# PowerBoard.net
KiCad netlist of a schematic drawn in Altium Designer
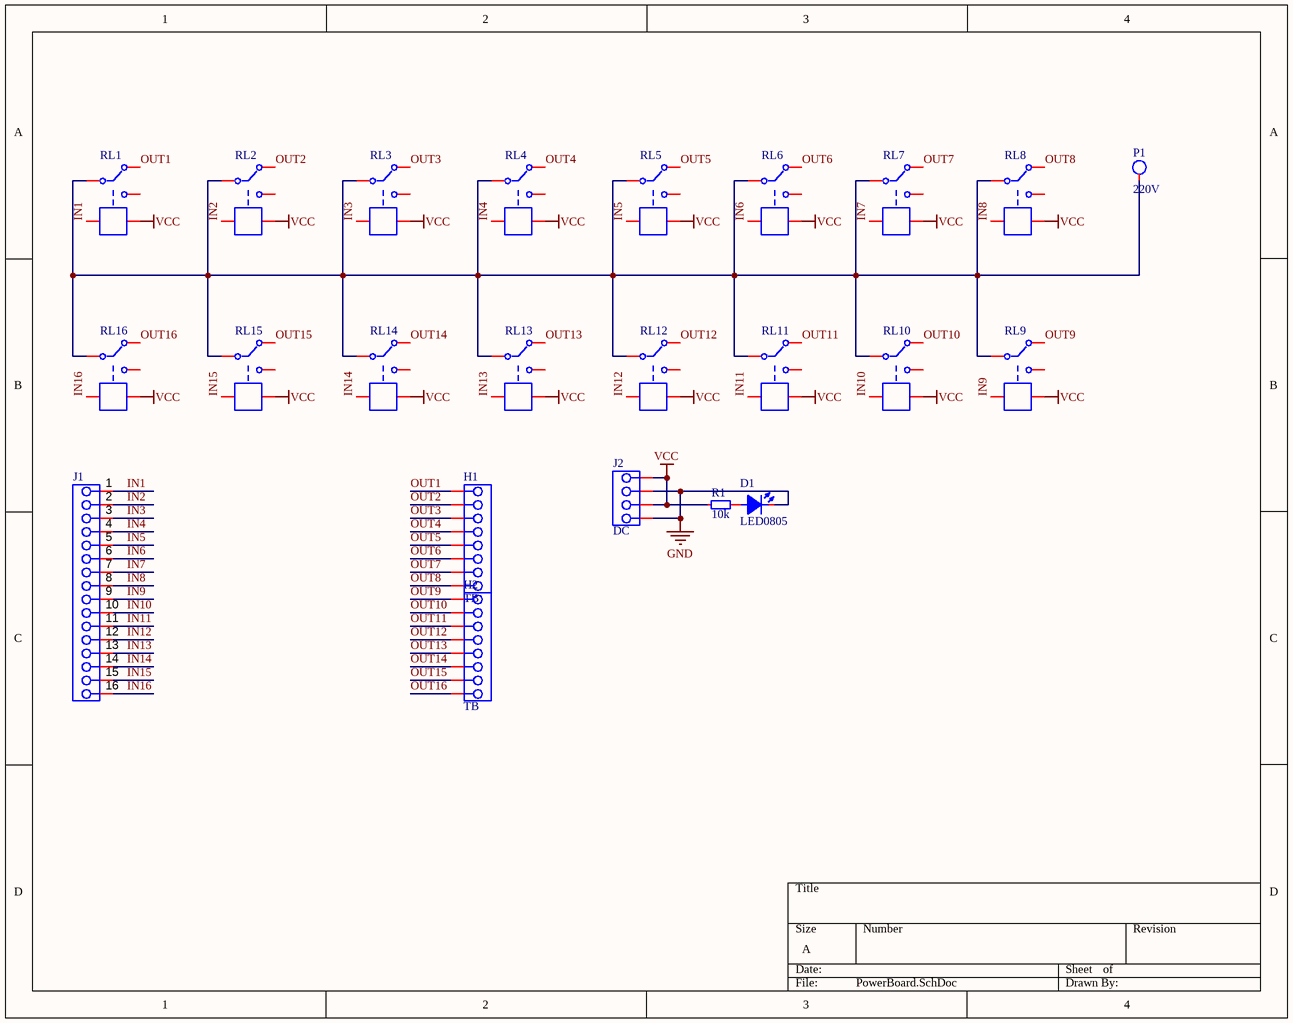
[diagram p0: PowerBoard.SchDoc]

(export (version "E")
  (design (tool "Eeschema 10.0.6"))
  (components
    (comp (ref "D1")
      (value "LED0805")
      (footprint "L0805RED")
      (libsource (lib "MyAltiumLibrary") (part "LED0805"))
    )
    (comp (ref "H1")
      (value "TB")
      (footprint "TERMINAL-BLOCK-7.62MM -08PIN")
      (libsource (lib "MyAltiumLibrary") (part "TERMINAL-BLOCK-7.62MM-08PIN"))
    )
    (comp (ref "H2")
      (value "TB")
      (footprint "TERMINAL-BLOCK-7.62MM -08PIN")
      (libsource (lib "MyAltiumLibrary") (part "TERMINAL-BLOCK-7.62MM-08PIN"))
    )
    (comp (ref "J1")
      (value "HEADER-FEMALE-2.54MM")
      (footprint "HEADER-FEMALE-16PINS-2.54MM")
      (libsource (lib "MyAltiumLibrary") (part "HEADER-FEMALE-16PINS-2.54MM"))
    )
    (comp (ref "J2")
      (value "DC")
      (footprint "DG350-3.5-04P-12-00AH")
      (libsource (lib "MyAltiumLibrary") (part "DGxxx_04P"))
    )
    (comp (ref "P1")
      (value "220V")
      (footprint "SolderPoint")
      (libsource (lib "MyAltiumLibrary") (part "SolderPoint"))
    )
    (comp (ref "R1")
      (value "10k")
      (footprint "R0805")
      (libsource (lib "MyAltiumLibrary") (part "Resistors-SMD"))
    )
    (comp (ref "RL1")
      (value "Relay-SONGLE-SRD-05VDC")
      (footprint "RELAY-SONGLE-SRD-05VDC_BLUE")
      (libsource (lib "MyAltiumLibrary") (part "Relay-SONGLE-SRD-05VDC"))
    )
    (comp (ref "RL2")
      (value "Relay-SONGLE-SRD-05VDC")
      (footprint "RELAY-SONGLE-SRD-05VDC_BLUE")
      (libsource (lib "MyAltiumLibrary") (part "Relay-SONGLE-SRD-05VDC"))
    )
    (comp (ref "RL3")
      (value "Relay-SONGLE-SRD-05VDC")
      (footprint "RELAY-SONGLE-SRD-05VDC_BLUE")
      (libsource (lib "MyAltiumLibrary") (part "Relay-SONGLE-SRD-05VDC"))
    )
    (comp (ref "RL4")
      (value "Relay-SONGLE-SRD-05VDC")
      (footprint "RELAY-SONGLE-SRD-05VDC_BLUE")
      (libsource (lib "MyAltiumLibrary") (part "Relay-SONGLE-SRD-05VDC"))
    )
    (comp (ref "RL5")
      (value "Relay-SONGLE-SRD-05VDC")
      (footprint "RELAY-SONGLE-SRD-05VDC_BLUE")
      (libsource (lib "MyAltiumLibrary") (part "Relay-SONGLE-SRD-05VDC"))
    )
    (comp (ref "RL6")
      (value "Relay-SONGLE-SRD-05VDC")
      (footprint "RELAY-SONGLE-SRD-05VDC_BLUE")
      (libsource (lib "MyAltiumLibrary") (part "Relay-SONGLE-SRD-05VDC"))
    )
    (comp (ref "RL7")
      (value "Relay-SONGLE-SRD-05VDC")
      (footprint "RELAY-SONGLE-SRD-05VDC_BLUE")
      (libsource (lib "MyAltiumLibrary") (part "Relay-SONGLE-SRD-05VDC"))
    )
    (comp (ref "RL8")
      (value "Relay-SONGLE-SRD-05VDC")
      (footprint "RELAY-SONGLE-SRD-05VDC_BLUE")
      (libsource (lib "MyAltiumLibrary") (part "Relay-SONGLE-SRD-05VDC"))
    )
    (comp (ref "RL9")
      (value "Relay-SONGLE-SRD-05VDC")
      (footprint "RELAY-SONGLE-SRD-05VDC_BLUE")
      (libsource (lib "MyAltiumLibrary") (part "Relay-SONGLE-SRD-05VDC"))
    )
    (comp (ref "RL10")
      (value "Relay-SONGLE-SRD-05VDC")
      (footprint "RELAY-SONGLE-SRD-05VDC_BLUE")
      (libsource (lib "MyAltiumLibrary") (part "Relay-SONGLE-SRD-05VDC"))
    )
    (comp (ref "RL11")
      (value "Relay-SONGLE-SRD-05VDC")
      (footprint "RELAY-SONGLE-SRD-05VDC_BLUE")
      (libsource (lib "MyAltiumLibrary") (part "Relay-SONGLE-SRD-05VDC"))
    )
    (comp (ref "RL12")
      (value "Relay-SONGLE-SRD-05VDC")
      (footprint "RELAY-SONGLE-SRD-05VDC_BLUE")
      (libsource (lib "MyAltiumLibrary") (part "Relay-SONGLE-SRD-05VDC"))
    )
    (comp (ref "RL13")
      (value "Relay-SONGLE-SRD-05VDC")
      (footprint "RELAY-SONGLE-SRD-05VDC_BLUE")
      (libsource (lib "MyAltiumLibrary") (part "Relay-SONGLE-SRD-05VDC"))
    )
    (comp (ref "RL14")
      (value "Relay-SONGLE-SRD-05VDC")
      (footprint "RELAY-SONGLE-SRD-05VDC_BLUE")
      (libsource (lib "MyAltiumLibrary") (part "Relay-SONGLE-SRD-05VDC"))
    )
    (comp (ref "RL15")
      (value "Relay-SONGLE-SRD-05VDC")
      (footprint "RELAY-SONGLE-SRD-05VDC_BLUE")
      (libsource (lib "MyAltiumLibrary") (part "Relay-SONGLE-SRD-05VDC"))
    )
    (comp (ref "RL16")
      (value "Relay-SONGLE-SRD-05VDC")
      (footprint "RELAY-SONGLE-SRD-05VDC_BLUE")
      (libsource (lib "MyAltiumLibrary") (part "Relay-SONGLE-SRD-05VDC"))
    )
  )
  (nets
    (net (code "1") (name "/IN1") (class "Default")
      (node (ref "J1") (pin "1") (pinfunction "1_1") (pintype "passive"))
      (node (ref "RL1") (pin "1") (pinfunction "1_1") (pintype "passive"))
    )
    (net (code "2") (name "/IN2") (class "Default")
      (node (ref "J1") (pin "2") (pinfunction "2_2") (pintype "passive"))
      (node (ref "RL2") (pin "1") (pinfunction "1_1") (pintype "passive"))
    )
    (net (code "3") (name "/IN3") (class "Default")
      (node (ref "J1") (pin "3") (pinfunction "3_3") (pintype "passive"))
      (node (ref "RL3") (pin "1") (pinfunction "1_1") (pintype "passive"))
    )
    (net (code "4") (name "/IN4") (class "Default")
      (node (ref "J1") (pin "4") (pinfunction "4_4") (pintype "passive"))
      (node (ref "RL4") (pin "1") (pinfunction "1_1") (pintype "passive"))
    )
    (net (code "5") (name "/IN5") (class "Default")
      (node (ref "J1") (pin "5") (pinfunction "5_5") (pintype "passive"))
      (node (ref "RL5") (pin "1") (pinfunction "1_1") (pintype "passive"))
    )
    (net (code "6") (name "/IN6") (class "Default")
      (node (ref "J1") (pin "6") (pinfunction "6_6") (pintype "passive"))
      (node (ref "RL6") (pin "1") (pinfunction "1_1") (pintype "passive"))
    )
    (net (code "7") (name "/IN7") (class "Default")
      (node (ref "J1") (pin "7") (pinfunction "7_7") (pintype "passive"))
      (node (ref "RL7") (pin "1") (pinfunction "1_1") (pintype "passive"))
    )
    (net (code "8") (name "/IN8") (class "Default")
      (node (ref "J1") (pin "8") (pinfunction "8_8") (pintype "passive"))
      (node (ref "RL8") (pin "1") (pinfunction "1_1") (pintype "passive"))
    )
    (net (code "9") (name "/IN9") (class "Default")
      (node (ref "J1") (pin "9") (pinfunction "9_9") (pintype "passive"))
      (node (ref "RL9") (pin "1") (pinfunction "1_1") (pintype "passive"))
    )
    (net (code "10") (name "/IN10") (class "Default")
      (node (ref "J1") (pin "10") (pinfunction "10_10") (pintype "passive"))
      (node (ref "RL10") (pin "1") (pinfunction "1_1") (pintype "passive"))
    )
    (net (code "11") (name "/IN11") (class "Default")
      (node (ref "J1") (pin "11") (pinfunction "11_11") (pintype "passive"))
      (node (ref "RL11") (pin "1") (pinfunction "1_1") (pintype "passive"))
    )
    (net (code "12") (name "/IN12") (class "Default")
      (node (ref "J1") (pin "12") (pinfunction "12_12") (pintype "passive"))
      (node (ref "RL12") (pin "1") (pinfunction "1_1") (pintype "passive"))
    )
    (net (code "13") (name "/IN13") (class "Default")
      (node (ref "J1") (pin "13") (pinfunction "13_13") (pintype "passive"))
      (node (ref "RL13") (pin "1") (pinfunction "1_1") (pintype "passive"))
    )
    (net (code "14") (name "/IN14") (class "Default")
      (node (ref "J1") (pin "14") (pinfunction "14_14") (pintype "passive"))
      (node (ref "RL14") (pin "1") (pinfunction "1_1") (pintype "passive"))
    )
    (net (code "15") (name "/IN15") (class "Default")
      (node (ref "J1") (pin "15") (pinfunction "15_15") (pintype "passive"))
      (node (ref "RL15") (pin "1") (pinfunction "1_1") (pintype "passive"))
    )
    (net (code "16") (name "/IN16") (class "Default")
      (node (ref "J1") (pin "16") (pinfunction "16_16") (pintype "passive"))
      (node (ref "RL16") (pin "1") (pinfunction "1_1") (pintype "passive"))
    )
    (net (code "17") (name "/OUT1") (class "Default")
      (node (ref "H1") (pin "8") (pinfunction "8_8") (pintype "passive"))
      (node (ref "RL1") (pin "5") (pinfunction "5_5") (pintype "passive"))
    )
    (net (code "18") (name "/OUT2") (class "Default")
      (node (ref "H1") (pin "7") (pinfunction "7_7") (pintype "passive"))
      (node (ref "RL2") (pin "5") (pinfunction "5_5") (pintype "passive"))
    )
    (net (code "19") (name "/OUT3") (class "Default")
      (node (ref "H1") (pin "6") (pinfunction "6_6") (pintype "passive"))
      (node (ref "RL3") (pin "5") (pinfunction "5_5") (pintype "passive"))
    )
    (net (code "20") (name "/OUT4") (class "Default")
      (node (ref "H1") (pin "5") (pinfunction "5_5") (pintype "passive"))
      (node (ref "RL4") (pin "5") (pinfunction "5_5") (pintype "passive"))
    )
    (net (code "21") (name "/OUT5") (class "Default")
      (node (ref "H1") (pin "4") (pinfunction "4_4") (pintype "passive"))
      (node (ref "RL5") (pin "5") (pinfunction "5_5") (pintype "passive"))
    )
    (net (code "22") (name "/OUT6") (class "Default")
      (node (ref "H1") (pin "3") (pinfunction "3_3") (pintype "passive"))
      (node (ref "RL6") (pin "5") (pinfunction "5_5") (pintype "passive"))
    )
    (net (code "23") (name "/OUT7") (class "Default")
      (node (ref "H1") (pin "2") (pinfunction "2_2") (pintype "passive"))
      (node (ref "RL7") (pin "5") (pinfunction "5_5") (pintype "passive"))
    )
    (net (code "24") (name "/OUT8") (class "Default")
      (node (ref "H1") (pin "1") (pinfunction "1_1") (pintype "passive"))
      (node (ref "RL8") (pin "5") (pinfunction "5_5") (pintype "passive"))
    )
    (net (code "25") (name "/OUT9") (class "Default")
      (node (ref "H2") (pin "8") (pinfunction "8_8") (pintype "passive"))
      (node (ref "RL9") (pin "5") (pinfunction "5_5") (pintype "passive"))
    )
    (net (code "26") (name "/OUT10") (class "Default")
      (node (ref "H2") (pin "7") (pinfunction "7_7") (pintype "passive"))
      (node (ref "RL10") (pin "5") (pinfunction "5_5") (pintype "passive"))
    )
    (net (code "27") (name "/OUT11") (class "Default")
      (node (ref "H2") (pin "6") (pinfunction "6_6") (pintype "passive"))
      (node (ref "RL11") (pin "5") (pinfunction "5_5") (pintype "passive"))
    )
    (net (code "28") (name "/OUT12") (class "Default")
      (node (ref "H2") (pin "5") (pinfunction "5_5") (pintype "passive"))
      (node (ref "RL12") (pin "5") (pinfunction "5_5") (pintype "passive"))
    )
    (net (code "29") (name "/OUT13") (class "Default")
      (node (ref "H2") (pin "4") (pinfunction "4_4") (pintype "passive"))
      (node (ref "RL13") (pin "5") (pinfunction "5_5") (pintype "passive"))
    )
    (net (code "30") (name "/OUT14") (class "Default")
      (node (ref "H2") (pin "3") (pinfunction "3_3") (pintype "passive"))
      (node (ref "RL14") (pin "5") (pinfunction "5_5") (pintype "passive"))
    )
    (net (code "31") (name "/OUT15") (class "Default")
      (node (ref "H2") (pin "2") (pinfunction "2_2") (pintype "passive"))
      (node (ref "RL15") (pin "5") (pinfunction "5_5") (pintype "passive"))
    )
    (net (code "32") (name "/OUT16") (class "Default")
      (node (ref "H2") (pin "1") (pinfunction "1_1") (pintype "passive"))
      (node (ref "RL16") (pin "5") (pinfunction "5_5") (pintype "passive"))
    )
    (net (code "33") (name "GND") (class "Default")
      (node (ref "D1") (pin "2") (pinfunction "K_2") (pintype "passive"))
      (node (ref "J2") (pin "2") (pinfunction "2_2") (pintype "passive"))
      (node (ref "J2") (pin "4") (pinfunction "4_4") (pintype "passive"))
    )
    (net (code "34") (name "Net-(D1-A)") (class "Default")
      (node (ref "D1") (pin "1") (pinfunction "A_1") (pintype "passive"))
      (node (ref "R1") (pin "2") (pinfunction "2_2") (pintype "passive"))
    )
    (net (code "35") (name "Net-(P1-Pad1)") (class "Default")
      (node (ref "P1") (pin "1") (pinfunction "1_1") (pintype "passive"))
      (node (ref "RL1") (pin "2") (pinfunction "2_2") (pintype "passive"))
      (node (ref "RL10") (pin "2") (pinfunction "2_2") (pintype "passive"))
      (node (ref "RL11") (pin "2") (pinfunction "2_2") (pintype "passive"))
      (node (ref "RL12") (pin "2") (pinfunction "2_2") (pintype "passive"))
      (node (ref "RL13") (pin "2") (pinfunction "2_2") (pintype "passive"))
      (node (ref "RL14") (pin "2") (pinfunction "2_2") (pintype "passive"))
      (node (ref "RL15") (pin "2") (pinfunction "2_2") (pintype "passive"))
      (node (ref "RL16") (pin "2") (pinfunction "2_2") (pintype "passive"))
      (node (ref "RL2") (pin "2") (pinfunction "2_2") (pintype "passive"))
      (node (ref "RL3") (pin "2") (pinfunction "2_2") (pintype "passive"))
      (node (ref "RL4") (pin "2") (pinfunction "2_2") (pintype "passive"))
      (node (ref "RL5") (pin "2") (pinfunction "2_2") (pintype "passive"))
      (node (ref "RL6") (pin "2") (pinfunction "2_2") (pintype "passive"))
      (node (ref "RL7") (pin "2") (pinfunction "2_2") (pintype "passive"))
      (node (ref "RL8") (pin "2") (pinfunction "2_2") (pintype "passive"))
      (node (ref "RL9") (pin "2") (pinfunction "2_2") (pintype "passive"))
    )
    (net (code "36") (name "VCC") (class "Default")
      (node (ref "J2") (pin "1") (pinfunction "1_1") (pintype "passive"))
      (node (ref "J2") (pin "3") (pinfunction "3_3") (pintype "passive"))
      (node (ref "R1") (pin "1") (pinfunction "1_1") (pintype "passive"))
      (node (ref "RL1") (pin "3") (pinfunction "3_3") (pintype "passive"))
      (node (ref "RL10") (pin "3") (pinfunction "3_3") (pintype "passive"))
      (node (ref "RL11") (pin "3") (pinfunction "3_3") (pintype "passive"))
      (node (ref "RL12") (pin "3") (pinfunction "3_3") (pintype "passive"))
      (node (ref "RL13") (pin "3") (pinfunction "3_3") (pintype "passive"))
      (node (ref "RL14") (pin "3") (pinfunction "3_3") (pintype "passive"))
      (node (ref "RL15") (pin "3") (pinfunction "3_3") (pintype "passive"))
      (node (ref "RL16") (pin "3") (pinfunction "3_3") (pintype "passive"))
      (node (ref "RL2") (pin "3") (pinfunction "3_3") (pintype "passive"))
      (node (ref "RL3") (pin "3") (pinfunction "3_3") (pintype "passive"))
      (node (ref "RL4") (pin "3") (pinfunction "3_3") (pintype "passive"))
      (node (ref "RL5") (pin "3") (pinfunction "3_3") (pintype "passive"))
      (node (ref "RL6") (pin "3") (pinfunction "3_3") (pintype "passive"))
      (node (ref "RL7") (pin "3") (pinfunction "3_3") (pintype "passive"))
      (node (ref "RL8") (pin "3") (pinfunction "3_3") (pintype "passive"))
      (node (ref "RL9") (pin "3") (pinfunction "3_3") (pintype "passive"))
    )
    (net (code "37") (name "unconnected-(RL1-Pad4)") (class "Default")
      (node (ref "RL1") (pin "4") (pinfunction "4_4") (pintype "passive"))
    )
    (net (code "38") (name "unconnected-(RL2-Pad4)") (class "Default")
      (node (ref "RL2") (pin "4") (pinfunction "4_4") (pintype "passive"))
    )
    (net (code "39") (name "unconnected-(RL3-Pad4)") (class "Default")
      (node (ref "RL3") (pin "4") (pinfunction "4_4") (pintype "passive"))
    )
    (net (code "40") (name "unconnected-(RL4-Pad4)") (class "Default")
      (node (ref "RL4") (pin "4") (pinfunction "4_4") (pintype "passive"))
    )
    (net (code "41") (name "unconnected-(RL5-Pad4)") (class "Default")
      (node (ref "RL5") (pin "4") (pinfunction "4_4") (pintype "passive"))
    )
    (net (code "42") (name "unconnected-(RL6-Pad4)") (class "Default")
      (node (ref "RL6") (pin "4") (pinfunction "4_4") (pintype "passive"))
    )
    (net (code "43") (name "unconnected-(RL7-Pad4)") (class "Default")
      (node (ref "RL7") (pin "4") (pinfunction "4_4") (pintype "passive"))
    )
    (net (code "44") (name "unconnected-(RL8-Pad4)") (class "Default")
      (node (ref "RL8") (pin "4") (pinfunction "4_4") (pintype "passive"))
    )
    (net (code "45") (name "unconnected-(RL9-Pad4)") (class "Default")
      (node (ref "RL9") (pin "4") (pinfunction "4_4") (pintype "passive"))
    )
    (net (code "46") (name "unconnected-(RL10-Pad4)") (class "Default")
      (node (ref "RL10") (pin "4") (pinfunction "4_4") (pintype "passive"))
    )
    (net (code "47") (name "unconnected-(RL11-Pad4)") (class "Default")
      (node (ref "RL11") (pin "4") (pinfunction "4_4") (pintype "passive"))
    )
    (net (code "48") (name "unconnected-(RL12-Pad4)") (class "Default")
      (node (ref "RL12") (pin "4") (pinfunction "4_4") (pintype "passive"))
    )
    (net (code "49") (name "unconnected-(RL13-Pad4)") (class "Default")
      (node (ref "RL13") (pin "4") (pinfunction "4_4") (pintype "passive"))
    )
    (net (code "50") (name "unconnected-(RL14-Pad4)") (class "Default")
      (node (ref "RL14") (pin "4") (pinfunction "4_4") (pintype "passive"))
    )
    (net (code "51") (name "unconnected-(RL15-Pad4)") (class "Default")
      (node (ref "RL15") (pin "4") (pinfunction "4_4") (pintype "passive"))
    )
    (net (code "52") (name "unconnected-(RL16-Pad4)") (class "Default")
      (node (ref "RL16") (pin "4") (pinfunction "4_4") (pintype "passive"))
    )
  )
)
